# PERIPHERAL.net
KiCad netlist of a schematic drawn in Altium Designer
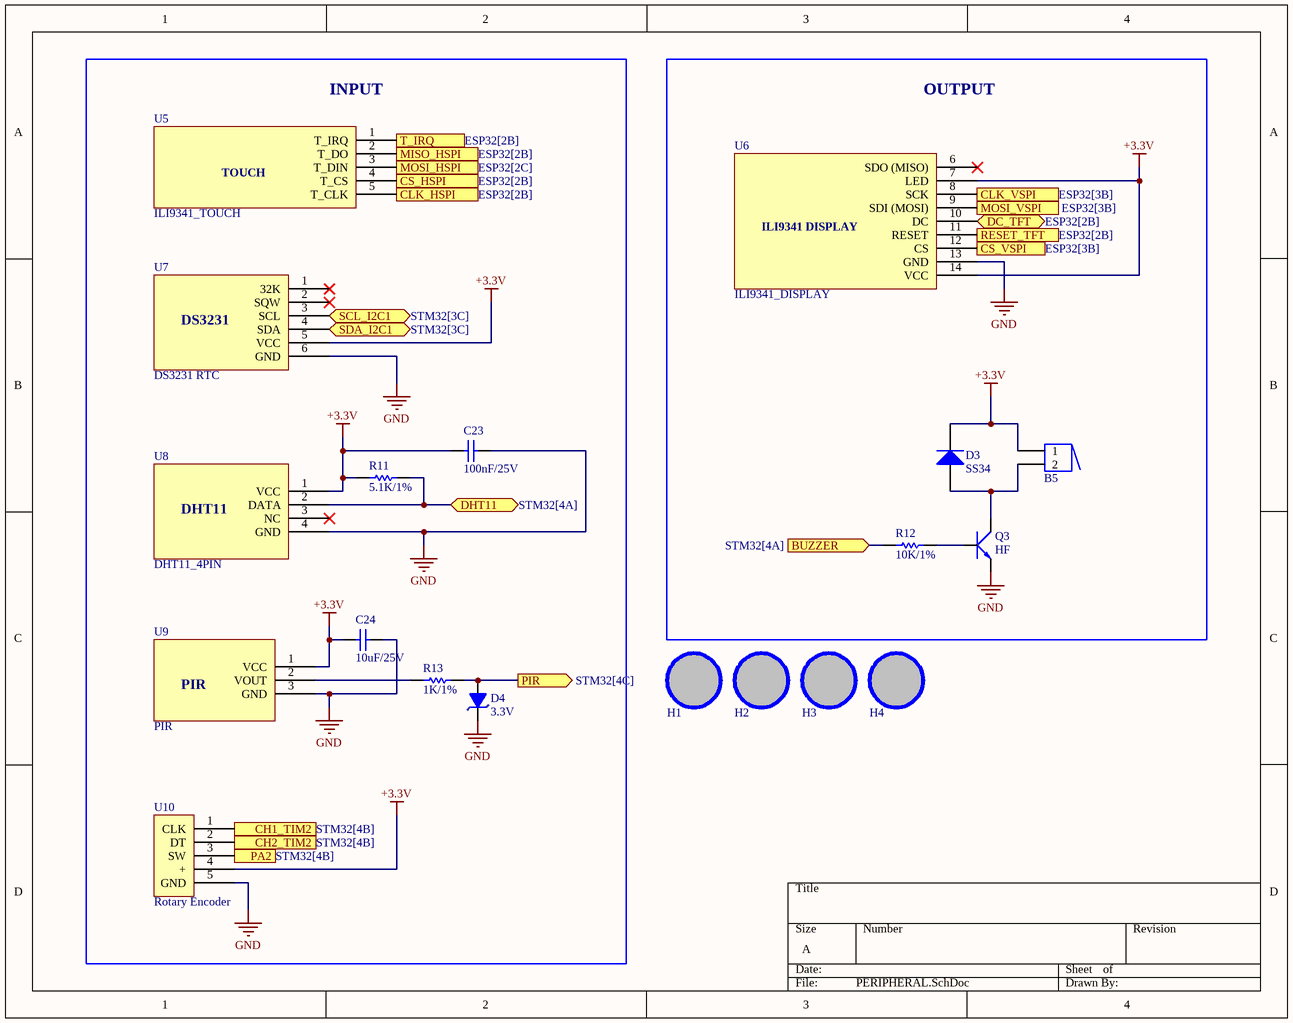
[diagram p0: PERIPHERAL.SchDoc]

(export (version "E")
  (design (tool "Eeschema 10.0.6"))
  (components
    (comp (ref "B5") (value "Buzzer") (footprint "BUZZER") (libsource (lib "PIF_Library") (part "Buzzer")))
    (comp (ref "C23")
      (value "100nF/25V")
      (footprint "CAP-SM-0805")
      (description "Capacitor")
      (fields (field (name "Comment") "Cap Non-Pol SMD"))
      (libsource (lib "PIF_Library") (part "Cap Non-Pol SMD"))
    )
    (comp (ref "C24")
      (value "10uF/25V")
      (footprint "CAP-SM-0805")
      (description "Capacitor")
      (fields (field (name "Comment") "Cap Non-Pol SMD"))
      (libsource (lib "PIF_Library") (part "Cap Non-Pol SMD"))
    )
    (comp (ref "D3")
      (value "SS34")
      (footprint "DIODE SMA")
      (description "Dán")
      (libsource (lib "Altium_Lib_by_KhueNguyenCreator") (part "Diode SS34 ( 1N5822 )"))
    )
    (comp (ref "D4")
      (value "3.3V")
      (footprint "DIODE ZENNER SMD SOD80")
      (description "Dán")
      (libsource (lib "Altium_Lib_by_KhueNguyenCreator") (part "Diode Zener 3.3V"))
    )
    (comp (ref "H1")
      (value "Hole")
      (footprint "LO KHOAN 3MM")
      (description "Hole 3mm")
      (libsource (lib "PIF_Library") (part "Hole"))
    )
    (comp (ref "H2")
      (value "Hole")
      (footprint "LO KHOAN 3MM")
      (description "Hole 3mm")
      (libsource (lib "PIF_Library") (part "Hole"))
    )
    (comp (ref "H3")
      (value "Hole")
      (footprint "LO KHOAN 3MM")
      (description "Hole 3mm")
      (libsource (lib "PIF_Library") (part "Hole"))
    )
    (comp (ref "H4")
      (value "Hole")
      (footprint "LO KHOAN 3MM")
      (description "Hole 3mm")
      (libsource (lib "PIF_Library") (part "Hole"))
    )
    (comp (ref "Q3")
      (value "HF")
      (footprint "SOT-23")
      (description "SOT-23")
      (libsource (lib "Altium_Lib_by_KhueNguyenCreator") (part "Trans C1815 HF SMD"))
    )
    (comp (ref "R11")
      (value "5.1K/1%")
      (footprint "RES-SM-0805")
      (description "Resistor")
      (fields (field (name "Comment") "RESISTOR SMD"))
      (libsource (lib "PIF_Library") (part "RESISTOR SMD"))
    )
    (comp (ref "R12")
      (value "10K/1%")
      (footprint "RES-SM-0805")
      (description "Resistor")
      (fields (field (name "Comment") "RESISTOR SMD"))
      (libsource (lib "PIF_Library") (part "RESISTOR SMD"))
    )
    (comp (ref "R13")
      (value "1K/1%")
      (footprint "RES-SM-0805")
      (description "Resistor")
      (fields (field (name "Comment") "RESISTOR SMD"))
      (libsource (lib "PIF_Library") (part "RESISTOR SMD"))
    )
    (comp (ref "U5")
      (value "ILI9341_TOUCH")
      (footprint "Header 5 Pin")
      (libsource (lib "Schematic") (part "ILI9341_TOUCH"))
    )
    (comp (ref "U6")
      (value "ILI9341_DISPLAY")
      (footprint "HEADER 9 PIN")
      (libsource (lib "Schematic") (part "ILI9341_DISPLAY"))
    )
    (comp (ref "U7")
      (value "DS3231 RTC")
      (footprint "header 6 pin")
      (description "DS3231 RTC Module")
      (libsource (lib "Schematic") (part "DS3231"))
    )
    (comp (ref "U8")
      (value "DHT11_4PIN")
      (footprint "Header 4 Pin")
      (libsource (lib "Schematic") (part "DHT11_4PIN"))
    )
    (comp (ref "U9") (value "PIR") (footprint "Header 3 Pin") (libsource (lib "Schematic") (part "PIR")))
    (comp (ref "U10")
      (value "Rotary Encoder")
      (footprint "Header 5 Pin")
      (libsource (lib "Schematic") (part "Rotary Encoder"))
    )
  )
  (nets
    (net (code "1") (name "+3.3V") (class "Default")
      (node (ref "B5") (pin "1") (pinfunction "1_1") (pintype "passive"))
      (node (ref "C23") (pin "2") (pinfunction "2_2") (pintype "passive"))
      (node (ref "C24") (pin "2") (pinfunction "2_2") (pintype "passive"))
      (node (ref "D3") (pin "2") (pinfunction "K_2") (pintype "passive"))
      (node (ref "R11") (pin "2") (pinfunction "2_2") (pintype "passive"))
      (node (ref "U10") (pin "4") (pinfunction "+_4") (pintype "passive"))
      (node (ref "U6") (pin "14") (pinfunction "VCC_14") (pintype "passive"))
      (node (ref "U6") (pin "7") (pinfunction "LED_7") (pintype "passive"))
      (node (ref "U7") (pin "5") (pinfunction "VCC_5") (pintype "passive"))
      (node (ref "U8") (pin "1") (pinfunction "VCC_1") (pintype "passive"))
      (node (ref "U9") (pin "1") (pinfunction "VCC_1") (pintype "passive"))
    )
    (net (code "2") (name "/BUZZER") (class "Default")
      (node (ref "R12") (pin "1") (pinfunction "1_1") (pintype "passive"))
    )
    (net (code "3") (name "/CH1_TIM2") (class "Default")
      (node (ref "U10") (pin "1") (pinfunction "CLK_1") (pintype "passive"))
    )
    (net (code "4") (name "/CH2_TIM2") (class "Default")
      (node (ref "U10") (pin "2") (pinfunction "DT_2") (pintype "passive"))
    )
    (net (code "5") (name "/CLK_HSPI") (class "Default")
      (node (ref "U5") (pin "5") (pinfunction "T_CLK_5") (pintype "passive"))
    )
    (net (code "6") (name "/CLK_VSPI") (class "Default")
      (node (ref "U6") (pin "8") (pinfunction "SCK_8") (pintype "passive"))
    )
    (net (code "7") (name "/CS_HSPI") (class "Default")
      (node (ref "U5") (pin "4") (pinfunction "T_CS_4") (pintype "passive"))
    )
    (net (code "8") (name "/CS_VSPI") (class "Default")
      (node (ref "U6") (pin "12") (pinfunction "CS_12") (pintype "passive"))
    )
    (net (code "9") (name "/DC_TFT") (class "Default")
      (node (ref "U6") (pin "10") (pinfunction "DC_10") (pintype "passive"))
    )
    (net (code "10") (name "/DHT11") (class "Default")
      (node (ref "R11") (pin "1") (pinfunction "1_1") (pintype "passive"))
      (node (ref "U8") (pin "2") (pinfunction "DATA_2") (pintype "passive"))
    )
    (net (code "11") (name "/MISO_HSPI") (class "Default")
      (node (ref "U5") (pin "2") (pinfunction "T_DO_2") (pintype "passive"))
    )
    (net (code "12") (name "/MOSI_HSPI") (class "Default")
      (node (ref "U5") (pin "3") (pinfunction "T_DIN_3") (pintype "passive"))
    )
    (net (code "13") (name "/MOSI_VSPI") (class "Default")
      (node (ref "U6") (pin "9") (pinfunction "SDI_(MOSI)_9") (pintype "passive"))
    )
    (net (code "14") (name "/PA2") (class "Default")
      (node (ref "U10") (pin "3") (pinfunction "SW_3") (pintype "passive"))
    )
    (net (code "15") (name "/PIR") (class "Default")
      (node (ref "D4") (pin "1") (pinfunction "A_1") (pintype "passive"))
      (node (ref "R13") (pin "2") (pinfunction "2_2") (pintype "passive"))
    )
    (net (code "16") (name "/RESET_TFT") (class "Default")
      (node (ref "U6") (pin "11") (pinfunction "RESET_11") (pintype "passive"))
    )
    (net (code "17") (name "/SCL_I2C1") (class "Default")
      (node (ref "U7") (pin "3") (pinfunction "SCL_3") (pintype "passive"))
    )
    (net (code "18") (name "/SDA_I2C1") (class "Default")
      (node (ref "U7") (pin "4") (pinfunction "SDA_4") (pintype "passive"))
    )
    (net (code "19") (name "/T_IRQ") (class "Default")
      (node (ref "U5") (pin "1") (pinfunction "T_IRQ_1") (pintype "passive"))
    )
    (net (code "20") (name "GND") (class "Default")
      (node (ref "C23") (pin "1") (pinfunction "1_1") (pintype "passive"))
      (node (ref "C24") (pin "1") (pinfunction "1_1") (pintype "passive"))
      (node (ref "D4") (pin "2") (pinfunction "K_2") (pintype "passive"))
      (node (ref "Q3") (pin "2") (pinfunction "E_2") (pintype "passive"))
      (node (ref "U10") (pin "5") (pinfunction "GND_5") (pintype "passive"))
      (node (ref "U6") (pin "13") (pinfunction "GND_13") (pintype "passive"))
      (node (ref "U7") (pin "6") (pinfunction "GND_6") (pintype "passive"))
      (node (ref "U8") (pin "4") (pinfunction "GND_4") (pintype "passive"))
      (node (ref "U9") (pin "3") (pinfunction "GND_3") (pintype "passive"))
    )
    (net (code "21") (name "Net-(D3-A)") (class "Default")
      (node (ref "B5") (pin "2") (pinfunction "2_2") (pintype "passive"))
      (node (ref "D3") (pin "1") (pinfunction "A_1") (pintype "passive"))
      (node (ref "Q3") (pin "3") (pinfunction "C_3") (pintype "passive"))
    )
    (net (code "22") (name "Net-(Q3-B)") (class "Default")
      (node (ref "Q3") (pin "1") (pinfunction "B_1") (pintype "passive"))
      (node (ref "R12") (pin "2") (pinfunction "2_2") (pintype "passive"))
    )
    (net (code "23") (name "Net-(U9-VOUT)") (class "Default")
      (node (ref "R13") (pin "1") (pinfunction "1_1") (pintype "passive"))
      (node (ref "U9") (pin "2") (pinfunction "VOUT_2") (pintype "passive"))
    )
    (net (code "24") (name "unconnected-(H1-Pad1)") (class "Default")
      (node (ref "H1") (pin "1") (pinfunction "1_1") (pintype "passive"))
    )
    (net (code "25") (name "unconnected-(H2-Pad1)") (class "Default")
      (node (ref "H2") (pin "1") (pinfunction "1_1") (pintype "passive"))
    )
    (net (code "26") (name "unconnected-(H3-Pad1)") (class "Default")
      (node (ref "H3") (pin "1") (pinfunction "1_1") (pintype "passive"))
    )
    (net (code "27") (name "unconnected-(H4-Pad1)") (class "Default")
      (node (ref "H4") (pin "1") (pinfunction "1_1") (pintype "passive"))
    )
    (net (code "28") (name "unconnected-(U6-SDO_(MISO)-Pad6)") (class "Default")
      (node (ref "U6") (pin "6") (pinfunction "SDO_(MISO)_6") (pintype "passive+no_connect"))
    )
    (net (code "29") (name "unconnected-(U7-32K-Pad1)") (class "Default")
      (node (ref "U7") (pin "1") (pinfunction "32K_1") (pintype "passive+no_connect"))
    )
    (net (code "30") (name "unconnected-(U7-SQW-Pad2)") (class "Default")
      (node (ref "U7") (pin "2") (pinfunction "SQW_2") (pintype "passive+no_connect"))
    )
    (net (code "31") (name "unconnected-(U8-NC-Pad3)") (class "Default")
      (node (ref "U8") (pin "3") (pinfunction "NC_3") (pintype "passive+no_connect"))
    )
  )
)
